# Sheet1.net
KiCad netlist of a schematic drawn in Altium Designer
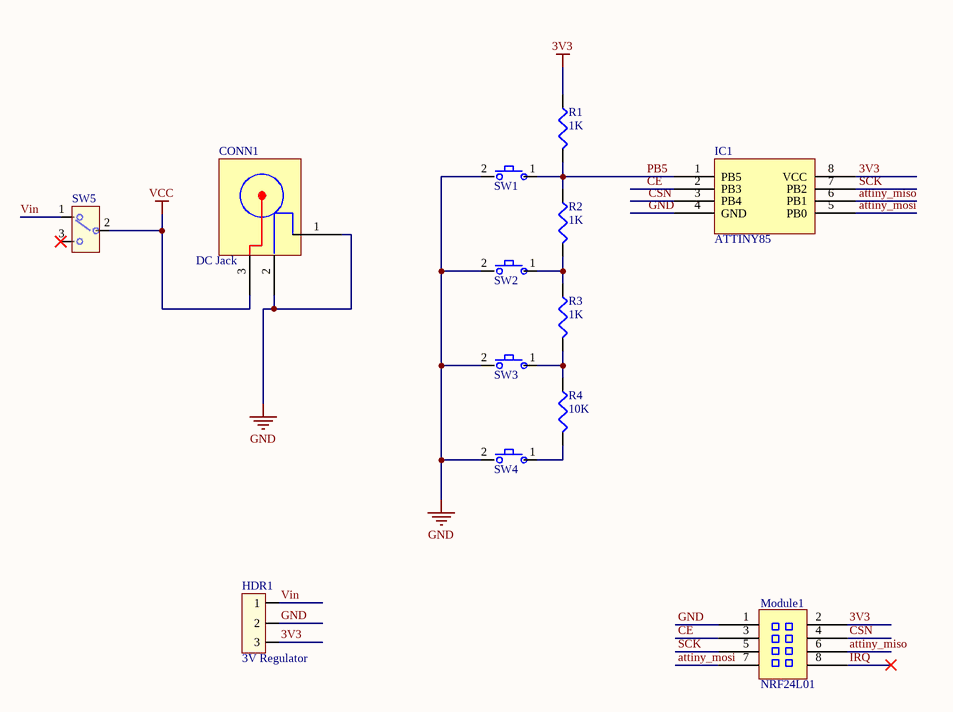
[diagram p0: Sheet1.SchDoc]

(export (version "E")
  (design (tool "Eeschema 10.0.6"))
  (components
    (comp (ref "CONN1")
      (value "DC Jack")
      (footprint "DC Jack")
      (description "CONN, 6mm Hole Size DC Jack")
      (libsource (lib "FX Component Library") (part "600035"))
    )
    (comp (ref "HDR1")
      (value "3V Regulator")
      (footprint "Header3 - SIMPLE")
      (description "HDR, Female 3-position")
      (libsource (lib "FX Component Library") (part "600032"))
    )
    (comp (ref "IC1")
      (value "ATTINY85")
      (footprint "PDIP-8")
      (description "IC, ATTINY85, PDIP-8")
      (libsource (lib "FX Component Library") (part "600027"))
    )
    (comp (ref "Module1")
      (value "NRF24L01")
      (footprint "Header8")
      (description "Module, Female HDR 8-Position")
      (libsource (lib "FX Component Library") (part "600030"))
    )
    (comp (ref "R1")
      (value "1K")
      (footprint "1608[0603]")
      (description "RES, Through Hole, 10K Ohm, ±1%, 1/2W")
      (fields (field (name "TOLERANCE") "±1%"))
      (libsource (lib "FX Component Library") (part "600002"))
    )
    (comp (ref "R2")
      (value "1K")
      (footprint "1608[0603]")
      (description "RES, Through Hole, 10K Ohm, ±1%, 1/2W")
      (fields (field (name "TOLERANCE") "±1%"))
      (libsource (lib "FX Component Library") (part "600002"))
    )
    (comp (ref "R3")
      (value "1K")
      (footprint "1608[0603]")
      (description "RES, Through Hole, 10K Ohm, ±1%, 1/2W")
      (fields (field (name "TOLERANCE") "±1%"))
      (libsource (lib "FX Component Library") (part "600002"))
    )
    (comp (ref "R4")
      (value "10K")
      (footprint "1608[0603]")
      (description "RES, Through Hole, 10K Ohm, ±1%, 1/2W")
      (fields (field (name "TOLERANCE") "±1%"))
      (libsource (lib "FX Component Library") (part "600002"))
    )
    (comp (ref "SW1")
      (value "517315R")
      (footprint "Push Button")
      (description "SW, NKKAB11AH-RO")
      (libsource (lib "FX Component Library") (part "517315R"))
    )
    (comp (ref "SW2")
      (value "517315R")
      (footprint "Push Button")
      (description "SW, NKKAB11AH-RO")
      (libsource (lib "FX Component Library") (part "517315R"))
    )
    (comp (ref "SW3")
      (value "517315R")
      (footprint "Push Button")
      (description "SW, NKKAB11AH-RO")
      (libsource (lib "FX Component Library") (part "517315R"))
    )
    (comp (ref "SW4")
      (value "517315R")
      (footprint "Push Button")
      (description "SW, NKKAB11AH-RO")
      (libsource (lib "FX Component Library") (part "517315R"))
    )
    (comp (ref "SW5")
      (value "600029")
      (footprint "Switch - small")
      (description "SW, Small, Through Hole SPDT Switch")
      (libsource (lib "FX Component Library") (part "600029"))
    )
  )
  (nets
    (net (code "1") (name "/CE") (class "Default")
      (node (ref "IC1") (pin "2") (pinfunction "PB3_2") (pintype "passive"))
      (node (ref "Module1") (pin "3") (pinfunction "3_3") (pintype "passive"))
    )
    (net (code "2") (name "/CSN") (class "Default")
      (node (ref "IC1") (pin "3") (pinfunction "PB4_3") (pintype "passive"))
      (node (ref "Module1") (pin "4") (pinfunction "4_4") (pintype "passive"))
    )
    (net (code "3") (name "/IRQ") (class "Default")
      (node (ref "Module1") (pin "8") (pinfunction "8_8") (pintype "passive+no_connect"))
    )
    (net (code "4") (name "/PB5") (class "Default")
      (node (ref "IC1") (pin "1") (pinfunction "PB5_1") (pintype "passive"))
      (node (ref "R1") (pin "2") (pinfunction "2_2") (pintype "passive"))
      (node (ref "R2") (pin "1") (pinfunction "1_1") (pintype "passive"))
      (node (ref "SW1") (pin "1") (pintype "passive"))
    )
    (net (code "5") (name "/SCK") (class "Default")
      (node (ref "IC1") (pin "7") (pinfunction "PB2_7") (pintype "passive"))
      (node (ref "Module1") (pin "5") (pinfunction "5_5") (pintype "passive"))
    )
    (net (code "6") (name "/Vin") (class "Default")
      (node (ref "HDR1") (pin "1") (pinfunction "1_1") (pintype "passive"))
      (node (ref "SW5") (pin "1") (pinfunction "1_1") (pintype "passive"))
    )
    (net (code "7") (name "/attiny_miso") (class "Default")
      (node (ref "IC1") (pin "6") (pinfunction "PB1_6") (pintype "passive"))
      (node (ref "Module1") (pin "6") (pinfunction "6_6") (pintype "passive"))
    )
    (net (code "8") (name "/attiny_mosi") (class "Default")
      (node (ref "IC1") (pin "5") (pinfunction "PB0_5") (pintype "passive"))
      (node (ref "Module1") (pin "7") (pinfunction "7_7") (pintype "passive"))
    )
    (net (code "9") (name "3V3") (class "Default")
      (node (ref "HDR1") (pin "3") (pinfunction "3_3") (pintype "passive"))
      (node (ref "IC1") (pin "8") (pinfunction "VCC_8") (pintype "passive"))
      (node (ref "Module1") (pin "2") (pinfunction "2_2") (pintype "passive"))
      (node (ref "R1") (pin "1") (pinfunction "1_1") (pintype "passive"))
    )
    (net (code "10") (name "GND") (class "Default")
      (node (ref "CONN1") (pin "1") (pinfunction "1_1") (pintype "passive"))
      (node (ref "CONN1") (pin "2") (pinfunction "2_2") (pintype "passive"))
      (node (ref "HDR1") (pin "2") (pinfunction "2_2") (pintype "passive"))
      (node (ref "IC1") (pin "4") (pinfunction "GND_4") (pintype "passive"))
      (node (ref "Module1") (pin "1") (pinfunction "1_1") (pintype "passive"))
      (node (ref "SW1") (pin "2") (pintype "passive"))
      (node (ref "SW2") (pin "2") (pintype "passive"))
      (node (ref "SW3") (pin "2") (pintype "passive"))
      (node (ref "SW4") (pin "2") (pintype "passive"))
    )
    (net (code "11") (name "Net-(R2-Pad2)") (class "Default")
      (node (ref "R2") (pin "2") (pinfunction "2_2") (pintype "passive"))
      (node (ref "R3") (pin "1") (pinfunction "1_1") (pintype "passive"))
      (node (ref "SW2") (pin "1") (pintype "passive"))
    )
    (net (code "12") (name "Net-(R3-Pad2)") (class "Default")
      (node (ref "R3") (pin "2") (pinfunction "2_2") (pintype "passive"))
      (node (ref "R4") (pin "1") (pinfunction "1_1") (pintype "passive"))
      (node (ref "SW3") (pin "1") (pintype "passive"))
    )
    (net (code "13") (name "Net-(R4-Pad2)") (class "Default")
      (node (ref "R4") (pin "2") (pinfunction "2_2") (pintype "passive"))
      (node (ref "SW4") (pin "1") (pintype "passive"))
    )
    (net (code "14") (name "VCC") (class "Default")
      (node (ref "CONN1") (pin "3") (pinfunction "3_3") (pintype "passive"))
      (node (ref "SW5") (pin "2") (pinfunction "2_2") (pintype "passive"))
    )
    (net (code "15") (name "unconnected-(SW5-Pad3)") (class "Default")
      (node (ref "SW5") (pin "3") (pinfunction "3_3") (pintype "passive+no_connect"))
    )
  )
)
